# SSFocuser-B-TMC2208-O.net
KiCad netlist of a schematic drawn in Altium Designer
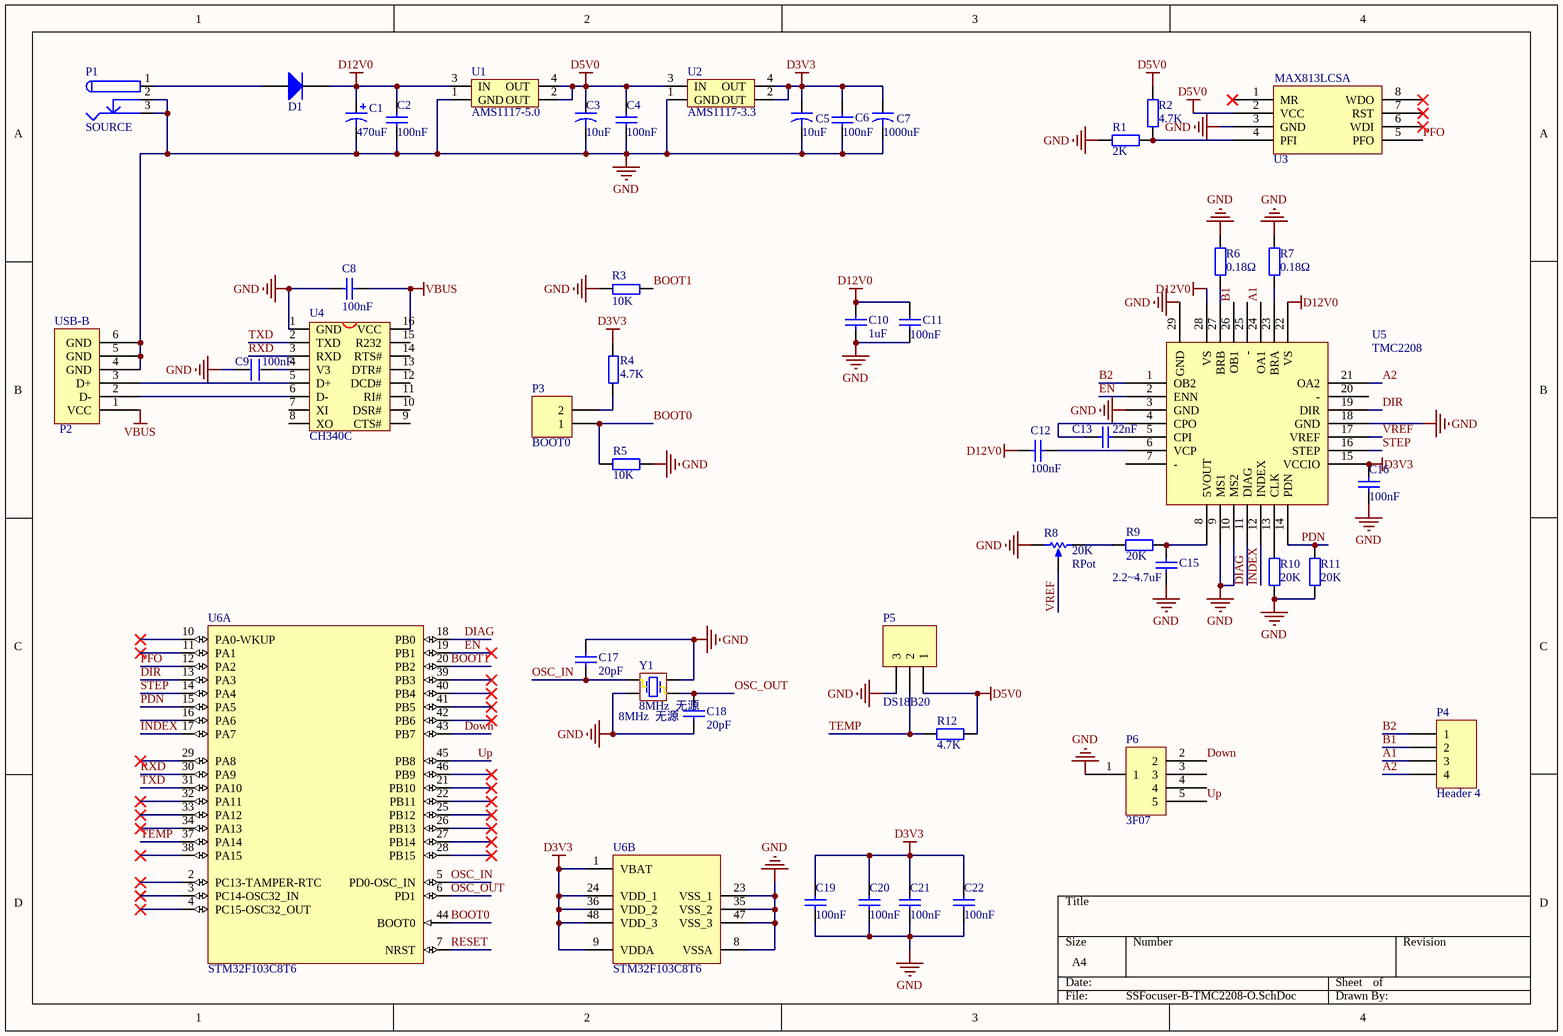
[diagram p0: SSFocuser-B-TMC2208-O.SchDoc]

(export (version "E")
  (design (tool "Eeschema 10.0.6"))
  (components
    (comp (ref "C1")
      (value "470uF")
      (footprint "16V/470U(CD10X10D5)")
      (description "470UF      16V      CD10X10D5")
      (libsource (lib "平台原理图symbol图库V1.0") (part "C470UF016S"))
    )
    (comp (ref "C2")
      (value "100nF")
      (footprint "0603C")
      (description "Capacitor")
      (fields (field (name "PUBLISHER") "Altium Limited"))
      (libsource (lib "Crazy_PCB") (part "Cap"))
    )
    (comp (ref "C3")
      (value "10uF")
      (footprint "3216")
      (fields (field (name "VAULE") "10uF"))
      (libsource (lib "Crazy_PCB") (part "CAP2"))
    )
    (comp (ref "C4")
      (value "100nF")
      (footprint "0603C")
      (description "Capacitor")
      (fields (field (name "PUBLISHER") "Altium Limited"))
      (libsource (lib "Crazy_PCB") (part "Cap"))
    )
    (comp (ref "C5")
      (value "10uF")
      (footprint "3216")
      (fields (field (name "VAULE") "10uF"))
      (libsource (lib "Crazy_PCB") (part "CAP2"))
    )
    (comp (ref "C6")
      (value "100nF")
      (footprint "0603C")
      (description "Capacitor")
      (fields (field (name "PUBLISHER") "Altium Limited"))
      (libsource (lib "Crazy_PCB") (part "Cap"))
    )
    (comp (ref "C7")
      (value "1000uF")
      (footprint "16V/470U(CD10X10D5)")
      (fields (field (name "VAULE") "1000uF"))
      (libsource (lib "Crazy_PCB") (part "CAP2"))
    )
    (comp (ref "C8")
      (value "100nF")
      (footprint "0603C")
      (description "Capacitor")
      (fields (field (name "PUBLISHER") "Altium Limited"))
      (libsource (lib "Crazy_PCB") (part "Cap"))
    )
    (comp (ref "C9")
      (value "100nF")
      (footprint "0603C")
      (libsource (lib "WarShip V3 STM32103封装库") (part "C"))
    )
    (comp (ref "C10")
      (value "1uF")
      (footprint "1206C")
      (description "Capacitor")
      (fields (field (name "PUBLISHER") "Altium Limited"))
      (libsource (lib "Crazy_PCB") (part "Cap"))
    )
    (comp (ref "C11")
      (value "100nF")
      (footprint "0603C")
      (description "Capacitor")
      (fields (field (name "PUBLISHER") "Altium Limited"))
      (libsource (lib "Crazy_PCB") (part "Cap"))
    )
    (comp (ref "C12")
      (value "100nF")
      (footprint "0603C")
      (description "Capacitor")
      (fields (field (name "PUBLISHER") "Altium Limited"))
      (libsource (lib "Crazy_PCB") (part "Cap"))
    )
    (comp (ref "C13")
      (value "22nF")
      (footprint "0603C")
      (description "Capacitor")
      (fields (field (name "PUBLISHER") "Altium Limited"))
      (libsource (lib "Crazy_PCB") (part "Cap"))
    )
    (comp (ref "C15")
      (value "2.2~4.7uF")
      (footprint "0603C")
      (description "Capacitor")
      (fields (field (name "PUBLISHER") "Altium Limited"))
      (libsource (lib "Crazy_PCB") (part "Cap"))
    )
    (comp (ref "C16")
      (value "100nF")
      (footprint "0603C")
      (description "Capacitor")
      (fields (field (name "PUBLISHER") "Altium Limited"))
      (libsource (lib "Crazy_PCB") (part "Cap"))
    )
    (comp (ref "C17")
      (value "20pF")
      (footprint "0603C")
      (description "Capacitor")
      (fields (field (name "PUBLISHER") "Altium Limited"))
      (libsource (lib "JL_SCH") (part "Cap"))
    )
    (comp (ref "C18")
      (value "20pF")
      (footprint "0603C")
      (description "Capacitor")
      (fields (field (name "PUBLISHER") "Altium Limited"))
      (libsource (lib "JL_SCH") (part "Cap"))
    )
    (comp (ref "C19")
      (value "100nF")
      (footprint "0603C")
      (description "Capacitor")
      (fields (field (name "PUBLISHER") "Altium Limited"))
      (libsource (lib "Crazy_PCB") (part "Cap"))
    )
    (comp (ref "C20")
      (value "100nF")
      (footprint "0603C")
      (description "Capacitor")
      (fields (field (name "PUBLISHER") "Altium Limited"))
      (libsource (lib "Crazy_PCB") (part "Cap"))
    )
    (comp (ref "C21")
      (value "100nF")
      (footprint "0603C")
      (description "Capacitor")
      (fields (field (name "PUBLISHER") "Altium Limited"))
      (libsource (lib "Crazy_PCB") (part "Cap"))
    )
    (comp (ref "C22")
      (value "100nF")
      (footprint "0603C")
      (description "Capacitor")
      (fields (field (name "PUBLISHER") "Altium Limited"))
      (libsource (lib "Crazy_PCB") (part "Cap"))
    )
    (comp (ref "D1")
      (value "M7")
      (footprint "DO-214AC")
      (description "High Conductance Fast Diode")
      (fields (field (name "PUBLISHER") "Altium Limited"))
      (libsource (lib "Crazy_PCB") (part "Diode"))
    )
    (comp (ref "P1")
      (value "SOURCE")
      (footprint "DC005")
      (fields (field (name "PUBLISHER") "Altium Limited"))
      (libsource (lib "Crazy_PCB") (part "SOURCE"))
    )
    (comp (ref "P2") (value "USB-B") (footprint "USB-B") (libsource (lib "DX") (part "USB-B")))
    (comp (ref "P3")
      (value "BOOT0")
      (footprint "HDR1X2")
      (description "Header, 2-Pin")
      (fields (field (name "PUBLISHER") "Altium Limited"))
      (libsource (lib "Miscellaneous Connectors") (part "MHDR1X2"))
    )
    (comp (ref "P4")
      (value "Header 4")
      (footprint "XH_4_V")
      (description "Header, 4-Pin")
      (fields (field (name "PUBLISHER") "Altium Limited"))
      (libsource (lib "Miscellaneous Connectors") (part "Header 4"))
    )
    (comp (ref "P5")
      (value "DS18B20")
      (footprint "TO-92B")
      (description "Header, 3-Pin")
      (fields (field (name "PUBLISHER") "Altium Limited"))
      (libsource (lib "Miscellaneous Connectors") (part "Header 3"))
    )
    (comp (ref "P6")
      (value "3F07")
      (footprint "3F07")
      (description "EarPhone3.5")
      (libsource (lib "SS") (part "3F07"))
    )
    (comp (ref "R1")
      (value "2K")
      (footprint "0603R")
      (description "Resistor")
      (fields (field (name "PUBLISHER") "Altium Limited"))
      (libsource (lib "") (part "RES_2"))
    )
    (comp (ref "R2")
      (value "4.7K")
      (footprint "0603R")
      (description "Resistor")
      (fields (field (name "PUBLISHER") "Altium Limited"))
      (libsource (lib "Crazy_PCB") (part "RES"))
    )
    (comp (ref "R3") (value "10K") (footprint "0603R") (libsource (lib "WarShip V3 STM32103封装库") (part "R")))
    (comp (ref "R4") (value "4.7K") (footprint "0603R") (libsource (lib "WarShip V3 STM32103封装库") (part "R")))
    (comp (ref "R5")
      (value "10K")
      (footprint "0603R")
      (description "Resistor")
      (fields (field (name "PUBLISHER") "Altium Limited"))
      (libsource (lib "") (part "RES_1"))
    )
    (comp (ref "R6")
      (value "0.18Ω")
      (footprint "1206R")
      (description "Resistor")
      (fields (field (name "PUBLISHER") "Altium Limited"))
      (libsource (lib "") (part "RES_3"))
    )
    (comp (ref "R7")
      (value "0.18Ω")
      (footprint "1206R")
      (description "Resistor")
      (fields (field (name "PUBLISHER") "Altium Limited"))
      (libsource (lib "") (part "RES_3"))
    )
    (comp (ref "R8")
      (value "RPot")
      (footprint "VR_SMD")
      (description "Potentiometer")
      (fields (field (name "ALTIUM_VALUE") "20K") (field (name "PUBLISHER") "Altium Limited"))
      (libsource (lib "Miscellaneous Devices") (part "RPot"))
    )
    (comp (ref "R9")
      (value "20K")
      (footprint "0603R")
      (description "Resistor")
      (fields (field (name "PUBLISHER") "Altium Limited"))
      (libsource (lib "") (part "RES_2"))
    )
    (comp (ref "R10")
      (value "20K")
      (footprint "0603R")
      (description "Resistor")
      (fields (field (name "PUBLISHER") "Altium Limited"))
      (libsource (lib "Crazy_PCB") (part "RES"))
    )
    (comp (ref "R11")
      (value "20K")
      (footprint "0603R")
      (description "Resistor")
      (fields (field (name "PUBLISHER") "Altium Limited"))
      (libsource (lib "Crazy_PCB") (part "RES"))
    )
    (comp (ref "R12")
      (value "4.7K")
      (footprint "0603R")
      (description "Resistor")
      (fields (field (name "PUBLISHER") "Altium Limited"))
      (libsource (lib "") (part "RES_1"))
    )
    (comp (ref "U1")
      (value "AMS1117-5.0")
      (footprint "SOT223")
      (libsource (lib "MiniSTM32 V3.0封装库") (part "AMS1117"))
    )
    (comp (ref "U2")
      (value "AMS1117-3.3")
      (footprint "SOT223")
      (libsource (lib "MiniSTM32 V3.0封装库") (part "AMS1117"))
    )
    (comp (ref "U3") (value "MAX813LCSA") (footprint "SOP-8") (libsource (lib "DX") (part "MAX813L")))
    (comp (ref "U4")
      (value "CH340C")
      (footprint "SO-16")
      (description "USB2UART")
      (libsource (lib "WarShip V3 STM32103封装库") (part "CH340G"))
    )
    (comp (ref "U5") (value "TMC2208") (footprint "QFN28") (libsource (lib "SS") (part "TMC2208")))
    (comp (ref "U6")
      (value "STM32F103C8T6")
      (footprint "LQFP48_N")
      (libsource (lib "STMicroelectronics STM32 F1") (part "STM32F103C8T6"))
    )
    (comp (ref "Y1")
      (value "8MHz  无源")
      (footprint "X3225")
      (description "Crystal Oscillator")
      (fields (field (name "ALTIUM_VALUE") "8MHz  无源") (field (name "PUBLISHER") "Altium Limited"))
      (libsource (lib "JL_SCH") (part "XTAL_1"))
    )
  )
  (nets
    (net (code "1") (name "/A1") (class "Default")
      (node (ref "P4") (pin "3") (pinfunction "3_3") (pintype "passive"))
      (node (ref "U5") (pin "24") (pinfunction "OA1_24") (pintype "passive"))
    )
    (net (code "2") (name "/A2") (class "Default")
      (node (ref "P4") (pin "4") (pinfunction "4_4") (pintype "passive"))
      (node (ref "U5") (pin "21") (pinfunction "OA2_21") (pintype "passive"))
    )
    (net (code "3") (name "/B1") (class "Default")
      (node (ref "P4") (pin "2") (pinfunction "2_2") (pintype "passive"))
      (node (ref "U5") (pin "26") (pinfunction "OB1_26") (pintype "passive"))
    )
    (net (code "4") (name "/B2") (class "Default")
      (node (ref "P4") (pin "1") (pinfunction "1_1") (pintype "passive"))
      (node (ref "U5") (pin "1") (pinfunction "OB2_1") (pintype "passive"))
    )
    (net (code "5") (name "/BOOT0") (class "Default")
      (node (ref "P3") (pin "1") (pinfunction "1_1") (pintype "passive"))
      (node (ref "R5") (pin "1") (pinfunction "1_1") (pintype "passive"))
      (node (ref "U6") (pin "44") (pinfunction "BOOT0_44") (pintype "input"))
    )
    (net (code "6") (name "/BOOT1") (class "Default")
      (node (ref "R3") (pin "2") (pintype "passive"))
      (node (ref "U6") (pin "20") (pinfunction "PB2_20") (pintype "bidirectional"))
    )
    (net (code "7") (name "/DIAG") (class "Default")
      (node (ref "U5") (pin "11") (pinfunction "DIAG_11") (pintype "passive"))
      (node (ref "U6") (pin "18") (pinfunction "PB0_18") (pintype "bidirectional"))
    )
    (net (code "8") (name "/DIR") (class "Default")
      (node (ref "U5") (pin "19") (pinfunction "DIR_19") (pintype "passive"))
      (node (ref "U6") (pin "13") (pinfunction "PA3_13") (pintype "bidirectional"))
    )
    (net (code "9") (name "/Down") (class "Default")
      (node (ref "P6") (pin "2") (pinfunction "2_2") (pintype "passive"))
      (node (ref "U6") (pin "43") (pinfunction "PB7_43") (pintype "bidirectional"))
    )
    (net (code "10") (name "/EN") (class "Default")
      (node (ref "U5") (pin "2") (pinfunction "ENN_2") (pintype "passive"))
      (node (ref "U6") (pin "19") (pinfunction "PB1_19") (pintype "bidirectional"))
    )
    (net (code "11") (name "/INDEX") (class "Default")
      (node (ref "U5") (pin "12") (pinfunction "INDEX_12") (pintype "passive"))
      (node (ref "U6") (pin "17") (pinfunction "PA7_17") (pintype "bidirectional"))
    )
    (net (code "12") (name "/OSC_IN") (class "Default")
      (node (ref "C17") (pin "1") (pinfunction "1_1") (pintype "passive"))
      (node (ref "U6") (pin "5") (pinfunction "PD0-OSC_IN_5") (pintype "bidirectional"))
      (node (ref "Y1") (pin "1") (pinfunction "OSC1_1") (pintype "passive"))
    )
    (net (code "13") (name "/OSC_OUT") (class "Default")
      (node (ref "C18") (pin "1") (pinfunction "1_1") (pintype "passive"))
      (node (ref "U6") (pin "6") (pinfunction "PD1_6") (pintype "bidirectional"))
      (node (ref "Y1") (pin "3") (pinfunction "OSC2_3") (pintype "passive"))
    )
    (net (code "14") (name "/PDN") (class "Default")
      (node (ref "R11") (pin "2") (pinfunction "2_2") (pintype "passive"))
      (node (ref "U5") (pin "14") (pinfunction "PDN_14") (pintype "passive"))
      (node (ref "U6") (pin "15") (pinfunction "PA5_15") (pintype "bidirectional"))
    )
    (net (code "15") (name "/PFO") (class "Default")
      (node (ref "U3") (pin "5") (pinfunction "PFO_5") (pintype "passive"))
      (node (ref "U6") (pin "12") (pinfunction "PA2_12") (pintype "bidirectional"))
    )
    (net (code "16") (name "/RESET") (class "Default")
      (node (ref "U6") (pin "7") (pinfunction "NRST_7") (pintype "bidirectional"))
    )
    (net (code "17") (name "/RXD") (class "Default")
      (node (ref "U4") (pin "3") (pinfunction "RXD_3") (pintype "passive"))
      (node (ref "U6") (pin "30") (pinfunction "PA9_30") (pintype "bidirectional"))
    )
    (net (code "18") (name "/STEP") (class "Default")
      (node (ref "U5") (pin "16") (pinfunction "STEP_16") (pintype "passive"))
      (node (ref "U6") (pin "14") (pinfunction "PA4_14") (pintype "bidirectional"))
    )
    (net (code "19") (name "/TEMP") (class "Default")
      (node (ref "P5") (pin "2") (pinfunction "2_2") (pintype "passive"))
      (node (ref "R12") (pin "1") (pinfunction "1_1") (pintype "passive"))
      (node (ref "U6") (pin "37") (pinfunction "PA14_37") (pintype "bidirectional"))
    )
    (net (code "20") (name "/TXD") (class "Default")
      (node (ref "U4") (pin "2") (pinfunction "TXD_2") (pintype "passive"))
      (node (ref "U6") (pin "31") (pinfunction "PA10_31") (pintype "bidirectional"))
    )
    (net (code "21") (name "/Up") (class "Default")
      (node (ref "P6") (pin "5") (pinfunction "5_5") (pintype "passive"))
      (node (ref "U6") (pin "45") (pinfunction "PB8_45") (pintype "bidirectional"))
    )
    (net (code "22") (name "/VREF") (class "Default")
      (node (ref "R8") (pin "3") (pinfunction "TAP_3") (pintype "passive"))
      (node (ref "U5") (pin "17") (pinfunction "VREF_17") (pintype "passive"))
    )
    (net (code "23") (name "D3V3") (class "Default")
      (node (ref "C16") (pin "2") (pinfunction "2_2") (pintype "passive"))
      (node (ref "C19") (pin "2") (pinfunction "2_2") (pintype "passive"))
      (node (ref "C20") (pin "2") (pinfunction "2_2") (pintype "passive"))
      (node (ref "C21") (pin "2") (pinfunction "2_2") (pintype "passive"))
      (node (ref "C22") (pin "2") (pinfunction "2_2") (pintype "passive"))
      (node (ref "C5") (pin "1") (pinfunction "1_1") (pintype "passive"))
      (node (ref "C6") (pin "2") (pinfunction "2_2") (pintype "passive"))
      (node (ref "C7") (pin "1") (pinfunction "1_1") (pintype "passive"))
      (node (ref "R4") (pin "2") (pintype "passive"))
      (node (ref "U2") (pin "2") (pinfunction "OUT_2") (pintype "passive"))
      (node (ref "U2") (pin "4") (pinfunction "OUT_4") (pintype "passive"))
      (node (ref "U5") (pin "15") (pinfunction "VCCIO_15") (pintype "passive"))
      (node (ref "U6") (pin "1") (pinfunction "VBAT_1") (pintype "power_in"))
      (node (ref "U6") (pin "24") (pinfunction "VDD_1_24") (pintype "power_in"))
      (node (ref "U6") (pin "36") (pinfunction "VDD_2_36") (pintype "power_in"))
      (node (ref "U6") (pin "48") (pinfunction "VDD_3_48") (pintype "power_in"))
      (node (ref "U6") (pin "9") (pinfunction "VDDA_9") (pintype "power_in"))
    )
    (net (code "24") (name "D5V0") (class "Default")
      (node (ref "C3") (pin "1") (pinfunction "1_1") (pintype "passive"))
      (node (ref "C4") (pin "2") (pinfunction "2_2") (pintype "passive"))
      (node (ref "P5") (pin "1") (pinfunction "1_1") (pintype "passive"))
      (node (ref "R12") (pin "2") (pinfunction "2_2") (pintype "passive"))
      (node (ref "R2") (pin "2") (pinfunction "2_2") (pintype "passive"))
      (node (ref "U1") (pin "2") (pinfunction "OUT_2") (pintype "passive"))
      (node (ref "U1") (pin "4") (pinfunction "OUT_4") (pintype "passive"))
      (node (ref "U2") (pin "3") (pinfunction "IN_3") (pintype "passive"))
      (node (ref "U3") (pin "2") (pinfunction "VCC_2") (pintype "passive"))
    )
    (net (code "25") (name "D12V0") (class "Default")
      (node (ref "C1") (pin "1") (pinfunction "1_1") (pintype "passive"))
      (node (ref "C10") (pin "1") (pinfunction "1_1") (pintype "passive"))
      (node (ref "C11") (pin "2") (pinfunction "2_2") (pintype "passive"))
      (node (ref "C12") (pin "2") (pinfunction "2_2") (pintype "passive"))
      (node (ref "C2") (pin "2") (pinfunction "2_2") (pintype "passive"))
      (node (ref "D1") (pin "2") (pinfunction "K_2") (pintype "passive"))
      (node (ref "U1") (pin "3") (pinfunction "IN_3") (pintype "passive"))
      (node (ref "U5") (pin "22") (pinfunction "VS_22") (pintype "passive"))
      (node (ref "U5") (pin "28") (pinfunction "VS_28") (pintype "passive"))
    )
    (net (code "26") (name "GND") (class "Default")
      (node (ref "C1") (pin "2") (pinfunction "2_2") (pintype "passive"))
      (node (ref "C10") (pin "2") (pinfunction "2_2") (pintype "passive"))
      (node (ref "C11") (pin "1") (pinfunction "1_1") (pintype "passive"))
      (node (ref "C15") (pin "1") (pinfunction "1_1") (pintype "passive"))
      (node (ref "C16") (pin "1") (pinfunction "1_1") (pintype "passive"))
      (node (ref "C17") (pin "2") (pinfunction "2_2") (pintype "passive"))
      (node (ref "C18") (pin "2") (pinfunction "2_2") (pintype "passive"))
      (node (ref "C19") (pin "1") (pinfunction "1_1") (pintype "passive"))
      (node (ref "C2") (pin "1") (pinfunction "1_1") (pintype "passive"))
      (node (ref "C20") (pin "1") (pinfunction "1_1") (pintype "passive"))
      (node (ref "C21") (pin "1") (pinfunction "1_1") (pintype "passive"))
      (node (ref "C22") (pin "1") (pinfunction "1_1") (pintype "passive"))
      (node (ref "C3") (pin "2") (pinfunction "2_2") (pintype "passive"))
      (node (ref "C4") (pin "1") (pinfunction "1_1") (pintype "passive"))
      (node (ref "C5") (pin "2") (pinfunction "2_2") (pintype "passive"))
      (node (ref "C6") (pin "1") (pinfunction "1_1") (pintype "passive"))
      (node (ref "C7") (pin "2") (pinfunction "2_2") (pintype "passive"))
      (node (ref "C8") (pin "1") (pinfunction "1_1") (pintype "passive"))
      (node (ref "C9") (pin "1") (pintype "passive"))
      (node (ref "P1") (pin "2") (pinfunction "2_2") (pintype "power_in"))
      (node (ref "P1") (pin "3") (pinfunction "3_3") (pintype "power_in"))
      (node (ref "P2") (pin "4") (pinfunction "GND_4") (pintype "passive"))
      (node (ref "P2") (pin "5") (pinfunction "GND_5") (pintype "passive"))
      (node (ref "P2") (pin "6") (pinfunction "GND_6") (pintype "passive"))
      (node (ref "P5") (pin "3") (pinfunction "3_3") (pintype "passive"))
      (node (ref "P6") (pin "1") (pinfunction "1_1") (pintype "passive"))
      (node (ref "R1") (pin "2") (pinfunction "2_2") (pintype "passive"))
      (node (ref "R10") (pin "1") (pinfunction "1_1") (pintype "passive"))
      (node (ref "R11") (pin "1") (pinfunction "1_1") (pintype "passive"))
      (node (ref "R3") (pin "1") (pintype "passive"))
      (node (ref "R5") (pin "2") (pinfunction "2_2") (pintype "passive"))
      (node (ref "R6") (pin "1") (pinfunction "1_1") (pintype "passive"))
      (node (ref "R7") (pin "1") (pinfunction "1_1") (pintype "passive"))
      (node (ref "R8") (pin "1") (pinfunction "TOP_1") (pintype "passive"))
      (node (ref "U1") (pin "1") (pinfunction "GND_1") (pintype "passive"))
      (node (ref "U2") (pin "1") (pinfunction "GND_1") (pintype "passive"))
      (node (ref "U3") (pin "3") (pinfunction "GND_3") (pintype "passive"))
      (node (ref "U4") (pin "1") (pinfunction "GND_1") (pintype "passive"))
      (node (ref "U5") (pin "10") (pinfunction "MS2_10") (pintype "passive"))
      (node (ref "U5") (pin "18") (pinfunction "GND_18") (pintype "passive"))
      (node (ref "U5") (pin "29") (pinfunction "GND_29") (pintype "passive"))
      (node (ref "U5") (pin "3") (pinfunction "GND_3") (pintype "passive"))
      (node (ref "U5") (pin "9") (pinfunction "MS1_9") (pintype "passive"))
      (node (ref "U6") (pin "23") (pinfunction "VSS_1_23") (pintype "power_in"))
      (node (ref "U6") (pin "35") (pinfunction "VSS_2_35") (pintype "power_in"))
      (node (ref "U6") (pin "47") (pinfunction "VSS_3_47") (pintype "power_in"))
      (node (ref "U6") (pin "8") (pinfunction "VSSA_8") (pintype "power_in"))
      (node (ref "Y1") (pin "2") (pinfunction "NA_2") (pintype "passive"))
      (node (ref "Y1") (pin "4") (pinfunction "NA_4") (pintype "passive"))
    )
    (net (code "27") (name "Net-(D1-A)") (class "Default")
      (node (ref "D1") (pin "1") (pinfunction "A_1") (pintype "passive"))
      (node (ref "P1") (pin "1") (pinfunction "1_1") (pintype "power_in"))
    )
    (net (code "28") (name "Net-(P2-D+)") (class "Default")
      (node (ref "P2") (pin "3") (pinfunction "D+_3") (pintype "passive"))
      (node (ref "U4") (pin "5") (pinfunction "D+_5") (pintype "passive"))
    )
    (net (code "29") (name "Net-(P2-D-)") (class "Default")
      (node (ref "P2") (pin "2") (pinfunction "D-_2") (pintype "passive"))
      (node (ref "U4") (pin "6") (pinfunction "D-_6") (pintype "passive"))
    )
    (net (code "30") (name "Net-(P3-Pad2)") (class "Default")
      (node (ref "P3") (pin "2") (pinfunction "2_2") (pintype "passive"))
      (node (ref "R4") (pin "1") (pintype "passive"))
    )
    (net (code "31") (name "Net-(R8-BOT)") (class "Default")
      (node (ref "R8") (pin "2") (pinfunction "BOT_2") (pintype "passive"))
      (node (ref "R9") (pin "2") (pinfunction "2_2") (pintype "passive"))
    )
    (net (code "32") (name "Net-(U3-PFI)") (class "Default")
      (node (ref "R1") (pin "1") (pinfunction "1_1") (pintype "passive"))
      (node (ref "R2") (pin "1") (pinfunction "1_1") (pintype "passive"))
      (node (ref "U3") (pin "4") (pinfunction "PFI_4") (pintype "passive"))
    )
    (net (code "33") (name "Net-(U4-V3)") (class "Default")
      (node (ref "C9") (pin "2") (pintype "passive"))
      (node (ref "U4") (pin "4") (pinfunction "V3_4") (pintype "passive"))
    )
    (net (code "34") (name "Net-(U5-5VOUT)") (class "Default")
      (node (ref "C15") (pin "2") (pinfunction "2_2") (pintype "passive"))
      (node (ref "R9") (pin "1") (pinfunction "1_1") (pintype "passive"))
      (node (ref "U5") (pin "8") (pinfunction "5VOUT_8") (pintype "passive"))
    )
    (net (code "35") (name "Net-(U5-BRA)") (class "Default")
      (node (ref "R7") (pin "2") (pinfunction "2_2") (pintype "passive"))
      (node (ref "U5") (pin "23") (pinfunction "BRA_23") (pintype "passive"))
    )
    (net (code "36") (name "Net-(U5-BRB)") (class "Default")
      (node (ref "R6") (pin "2") (pinfunction "2_2") (pintype "passive"))
      (node (ref "U5") (pin "27") (pinfunction "BRB_27") (pintype "passive"))
    )
    (net (code "37") (name "Net-(U5-CLK)") (class "Default")
      (node (ref "R10") (pin "2") (pinfunction "2_2") (pintype "passive"))
      (node (ref "U5") (pin "13") (pinfunction "CLK_13") (pintype "passive"))
    )
    (net (code "38") (name "Net-(U5-CPI)") (class "Default")
      (node (ref "C13") (pin "1") (pinfunction "1_1") (pintype "passive"))
      (node (ref "U5") (pin "5") (pinfunction "CPI_5") (pintype "passive"))
    )
    (net (code "39") (name "Net-(U5-CPO)") (class "Default")
      (node (ref "C13") (pin "2") (pinfunction "2_2") (pintype "passive"))
      (node (ref "U5") (pin "4") (pinfunction "CPO_4") (pintype "passive"))
    )
    (net (code "40") (name "Net-(U5-VCP)") (class "Default")
      (node (ref "C12") (pin "1") (pinfunction "1_1") (pintype "passive"))
      (node (ref "U5") (pin "6") (pinfunction "VCP_6") (pintype "passive"))
    )
    (net (code "41") (name "VBUS") (class "Default")
      (node (ref "C8") (pin "2") (pinfunction "2_2") (pintype "passive"))
      (node (ref "P2") (pin "1") (pinfunction "VCC_1") (pintype "passive"))
      (node (ref "U4") (pin "16") (pinfunction "VCC_16") (pintype "passive"))
    )
    (net (code "42") (name "unconnected-(P6-Pad3)") (class "Default")
      (node (ref "P6") (pin "3") (pinfunction "3_3") (pintype "passive"))
    )
    (net (code "43") (name "unconnected-(P6-Pad4)") (class "Default")
      (node (ref "P6") (pin "4") (pinfunction "4_4") (pintype "passive"))
    )
    (net (code "44") (name "unconnected-(U3-MR-Pad1)") (class "Default")
      (node (ref "U3") (pin "1") (pinfunction "MR_1") (pintype "passive+no_connect"))
    )
    (net (code "45") (name "unconnected-(U3-RST-Pad7)") (class "Default")
      (node (ref "U3") (pin "7") (pinfunction "RST_7") (pintype "passive+no_connect"))
    )
    (net (code "46") (name "unconnected-(U3-WDI-Pad6)") (class "Default")
      (node (ref "U3") (pin "6") (pinfunction "WDI_6") (pintype "passive+no_connect"))
    )
    (net (code "47") (name "unconnected-(U3-WDO-Pad8)") (class "Default")
      (node (ref "U3") (pin "8") (pinfunction "WDO_8") (pintype "passive+no_connect"))
    )
    (net (code "48") (name "unconnected-(U4-CTS#-Pad9)") (class "Default")
      (node (ref "U4") (pin "9") (pinfunction "CTS#_9") (pintype "passive"))
    )
    (net (code "49") (name "unconnected-(U4-DCD#-Pad12)") (class "Default")
      (node (ref "U4") (pin "12") (pinfunction "DCD#_12") (pintype "passive"))
    )
    (net (code "50") (name "unconnected-(U4-DSR#-Pad10)") (class "Default")
      (node (ref "U4") (pin "10") (pinfunction "DSR#_10") (pintype "passive"))
    )
    (net (code "51") (name "unconnected-(U4-DTR#-Pad13)") (class "Default")
      (node (ref "U4") (pin "13") (pinfunction "DTR#_13") (pintype "passive"))
    )
    (net (code "52") (name "unconnected-(U4-R232-Pad15)") (class "Default")
      (node (ref "U4") (pin "15") (pinfunction "R232_15") (pintype "passive"))
    )
    (net (code "53") (name "unconnected-(U4-RI#-Pad11)") (class "Default")
      (node (ref "U4") (pin "11") (pinfunction "RI#_11") (pintype "passive"))
    )
    (net (code "54") (name "unconnected-(U4-RTS#-Pad14)") (class "Default")
      (node (ref "U4") (pin "14") (pinfunction "RTS#_14") (pintype "passive"))
    )
    (net (code "55") (name "unconnected-(U4-XI-Pad7)") (class "Default")
      (node (ref "U4") (pin "7") (pinfunction "XI_7") (pintype "passive"))
    )
    (net (code "56") (name "unconnected-(U4-XO-Pad8)") (class "Default")
      (node (ref "U4") (pin "8") (pinfunction "XO_8") (pintype "passive"))
    )
    (net (code "57") (name "unconnected-(U5---Pad7)") (class "Default")
      (node (ref "U5") (pin "7") (pinfunction "-_7") (pintype "passive"))
    )
    (net (code "58") (name "unconnected-(U5---Pad20)") (class "Default")
      (node (ref "U5") (pin "20") (pinfunction "-_20") (pintype "passive"))
    )
    (net (code "59") (name "unconnected-(U5---Pad25)") (class "Default")
      (node (ref "U5") (pin "25") (pinfunction "-_25") (pintype "passive"))
    )
    (net (code "60") (name "unconnected-(U6A-PA0-WKUP-Pad10)") (class "Default")
      (node (ref "U6") (pin "10") (pinfunction "PA0-WKUP_10") (pintype "bidirectional+no_connect"))
    )
    (net (code "61") (name "unconnected-(U6A-PA1-Pad11)") (class "Default")
      (node (ref "U6") (pin "11") (pinfunction "PA1_11") (pintype "bidirectional+no_connect"))
    )
    (net (code "62") (name "unconnected-(U6A-PA6-Pad16)") (class "Default")
      (node (ref "U6") (pin "16") (pinfunction "PA6_16") (pintype "bidirectional"))
    )
    (net (code "63") (name "unconnected-(U6A-PA8-Pad29)") (class "Default")
      (node (ref "U6") (pin "29") (pinfunction "PA8_29") (pintype "bidirectional+no_connect"))
    )
    (net (code "64") (name "unconnected-(U6A-PA11-Pad32)") (class "Default")
      (node (ref "U6") (pin "32") (pinfunction "PA11_32") (pintype "bidirectional+no_connect"))
    )
    (net (code "65") (name "unconnected-(U6A-PA12-Pad33)") (class "Default")
      (node (ref "U6") (pin "33") (pinfunction "PA12_33") (pintype "bidirectional+no_connect"))
    )
    (net (code "66") (name "unconnected-(U6A-PA13-Pad34)") (class "Default")
      (node (ref "U6") (pin "34") (pinfunction "PA13_34") (pintype "bidirectional+no_connect"))
    )
    (net (code "67") (name "unconnected-(U6A-PA15-Pad38)") (class "Default")
      (node (ref "U6") (pin "38") (pinfunction "PA15_38") (pintype "bidirectional+no_connect"))
    )
    (net (code "68") (name "unconnected-(U6A-PB3-Pad39)") (class "Default")
      (node (ref "U6") (pin "39") (pinfunction "PB3_39") (pintype "bidirectional+no_connect"))
    )
    (net (code "69") (name "unconnected-(U6A-PB4-Pad40)") (class "Default")
      (node (ref "U6") (pin "40") (pinfunction "PB4_40") (pintype "bidirectional+no_connect"))
    )
    (net (code "70") (name "unconnected-(U6A-PB5-Pad41)") (class "Default")
      (node (ref "U6") (pin "41") (pinfunction "PB5_41") (pintype "bidirectional+no_connect"))
    )
    (net (code "71") (name "unconnected-(U6A-PB6-Pad42)") (class "Default")
      (node (ref "U6") (pin "42") (pinfunction "PB6_42") (pintype "bidirectional+no_connect"))
    )
    (net (code "72") (name "unconnected-(U6A-PB9-Pad46)") (class "Default")
      (node (ref "U6") (pin "46") (pinfunction "PB9_46") (pintype "bidirectional+no_connect"))
    )
    (net (code "73") (name "unconnected-(U6A-PB10-Pad21)") (class "Default")
      (node (ref "U6") (pin "21") (pinfunction "PB10_21") (pintype "bidirectional+no_connect"))
    )
    (net (code "74") (name "unconnected-(U6A-PB11-Pad22)") (class "Default")
      (node (ref "U6") (pin "22") (pinfunction "PB11_22") (pintype "bidirectional+no_connect"))
    )
    (net (code "75") (name "unconnected-(U6A-PB12-Pad25)") (class "Default")
      (node (ref "U6") (pin "25") (pinfunction "PB12_25") (pintype "bidirectional+no_connect"))
    )
    (net (code "76") (name "unconnected-(U6A-PB13-Pad26)") (class "Default")
      (node (ref "U6") (pin "26") (pinfunction "PB13_26") (pintype "bidirectional+no_connect"))
    )
    (net (code "77") (name "unconnected-(U6A-PB14-Pad27)") (class "Default")
      (node (ref "U6") (pin "27") (pinfunction "PB14_27") (pintype "bidirectional+no_connect"))
    )
    (net (code "78") (name "unconnected-(U6A-PB15-Pad28)") (class "Default")
      (node (ref "U6") (pin "28") (pinfunction "PB15_28") (pintype "bidirectional+no_connect"))
    )
    (net (code "79") (name "unconnected-(U6A-PC13-TAMPER-RTC-Pad2)") (class "Default")
      (node (ref "U6") (pin "2") (pinfunction "PC13-TAMPER-RTC_2") (pintype "bidirectional+no_connect"))
    )
    (net (code "80") (name "unconnected-(U6A-PC14-OSC32_IN-Pad3)") (class "Default")
      (node (ref "U6") (pin "3") (pinfunction "PC14-OSC32_IN_3") (pintype "bidirectional+no_connect"))
    )
    (net (code "81") (name "unconnected-(U6A-PC15-OSC32_OUT-Pad4)") (class "Default")
      (node (ref "U6") (pin "4") (pinfunction "PC15-OSC32_OUT_4") (pintype "bidirectional+no_connect"))
    )
  )
)
